# Viehmann_GPS_2015.net
KiCad netlist of a schematic drawn in EAGLE
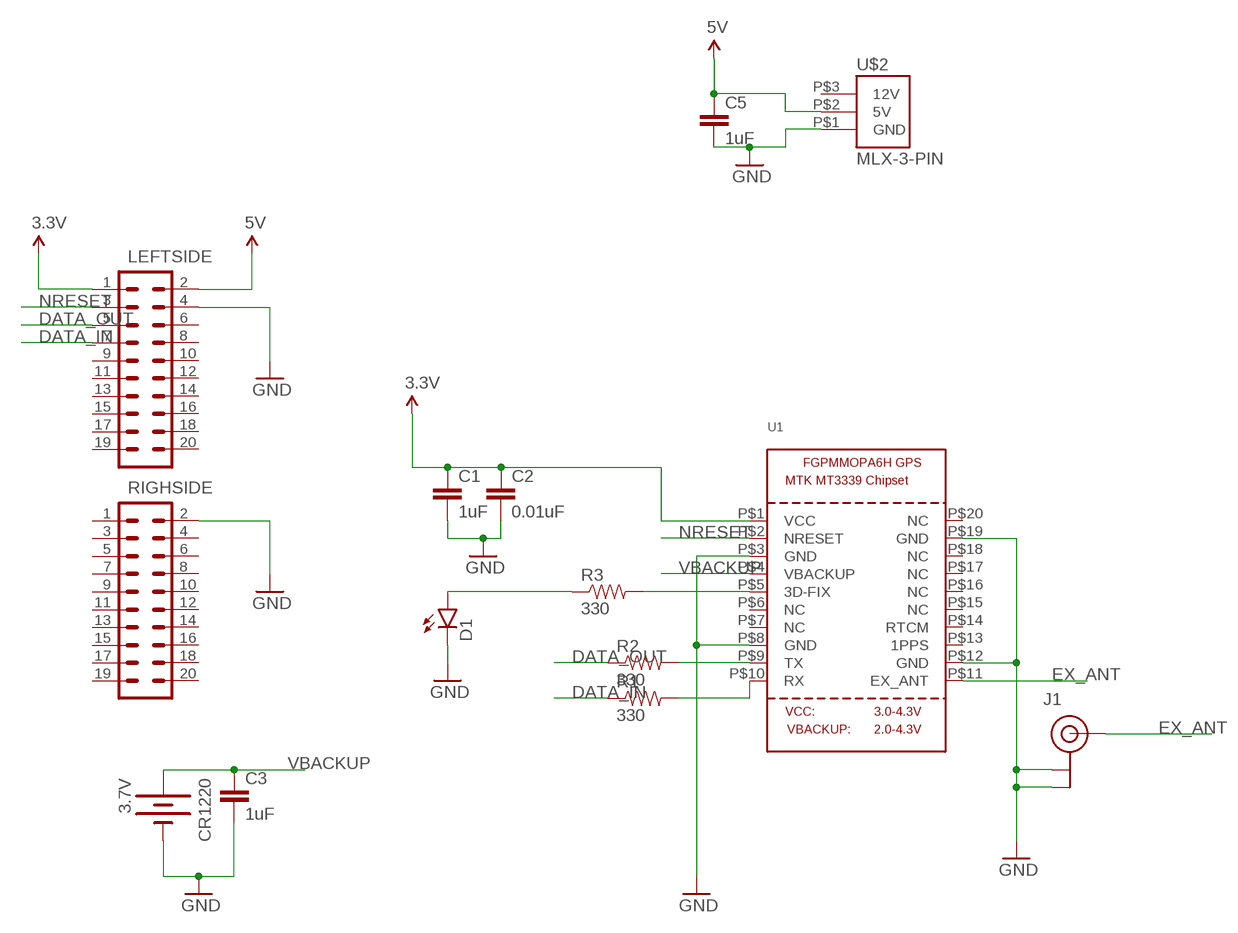
[diagram p0: schematic, sheet 1]

(export (version "E")
  (design (tool "Eeschema 10.0.6"))
  (components
    (comp (ref "C1")
      (value "1uF")
      (footprint "eagle-import:1206")
      (libsource (lib "eagle-import") (part "CAP1206"))
    )
    (comp (ref "C2")
      (value "0.01uF")
      (footprint "eagle-import:1206")
      (libsource (lib "eagle-import") (part "CAP1206"))
    )
    (comp (ref "C3")
      (value "1uF")
      (footprint "eagle-import:1206")
      (libsource (lib "eagle-import") (part "CAP1206"))
    )
    (comp (ref "C5")
      (value "1uF")
      (footprint "eagle-import:1206")
      (libsource (lib "eagle-import") (part "CAP1206"))
    )
    (comp (ref "CR1220")
      (value "3.7V")
      (footprint "eagle-import:BATTCON_12MM")
      (libsource (lib "eagle-import") (part "BATTERY12MM"))
    )
    (comp (ref "D1")
      (value "LED1206")
      (footprint "eagle-import:LED-1206")
      (libsource (lib "eagle-import") (part "LED1206"))
    )
    (comp (ref "J1")
      (value "U.FL")
      (footprint "eagle-import:U.FL")
      (libsource (lib "eagle-import") (part "U.FL"))
    )
    (comp (ref "LEFTSIDE")
      (value "M10X2")
      (footprint "eagle-import:2X10")
      (libsource (lib "eagle-import") (part "M10X2"))
    )
    (comp (ref "R1")
      (value "330")
      (footprint "eagle-import:1206")
      (libsource (lib "eagle-import") (part "RESISTOR1206"))
    )
    (comp (ref "R2")
      (value "330")
      (footprint "eagle-import:1206")
      (libsource (lib "eagle-import") (part "RESISTOR1206"))
    )
    (comp (ref "R3")
      (value "330")
      (footprint "eagle-import:1206")
      (libsource (lib "eagle-import") (part "RESISTOR1206"))
    )
    (comp (ref "RIGHSIDE")
      (value "M10X2")
      (footprint "eagle-import:2X10")
      (libsource (lib "eagle-import") (part "M10X2"))
    )
    (comp (ref "U$2")
      (value "MLX-3-PIN")
      (footprint "eagle-import:MLX-3-PIN-SOCKET")
      (libsource (lib "eagle-import") (part "MLX-3-PIN"))
    )
    (comp (ref "U1")
      (value "GPS_FGPMMOPA6H")
      (footprint "eagle-import:FGPMMOPA6H")
      (libsource (lib "eagle-import") (part "GPS_FGPMMOPA6H"))
    )
  )
  (nets
    (net (code "1") (name "/DATA_IN") (class "Default")
      (node (ref "LEFTSIDE") (pin "7") (pinfunction "7_7") (pintype "passive"))
      (node (ref "R1") (pin "1") (pinfunction "1_1") (pintype "passive"))
    )
    (net (code "2") (name "/DATA_OUT") (class "Default")
      (node (ref "LEFTSIDE") (pin "5") (pinfunction "5_5") (pintype "passive"))
      (node (ref "R2") (pin "1") (pinfunction "1_1") (pintype "passive"))
    )
    (net (code "3") (name "/EX_ANT") (class "Default")
      (node (ref "J1") (pin "P$3") (pinfunction "SIGNAL_P$3") (pintype "bidirectional"))
      (node (ref "U1") (pin "P$11") (pinfunction "EX_ANT_P$11") (pintype "bidirectional"))
    )
    (net (code "4") (name "/NRESET") (class "Default")
      (node (ref "LEFTSIDE") (pin "3") (pinfunction "3_3") (pintype "passive"))
      (node (ref "U1") (pin "P$2") (pinfunction "NRESET_P$2") (pintype "bidirectional"))
    )
    (net (code "5") (name "/VBACKUP") (class "Default")
      (node (ref "C3") (pin "1") (pinfunction "1_1") (pintype "passive"))
      (node (ref "CR1220") (pin "PWR@1") (pinfunction "+_PWR@1") (pintype "power_in"))
      (node (ref "U1") (pin "P$4") (pinfunction "VBACKUP_P$4") (pintype "bidirectional"))
    )
    (net (code "6") (name "3.3V") (class "Default")
      (node (ref "C1") (pin "1") (pinfunction "1_1") (pintype "passive"))
      (node (ref "C2") (pin "1") (pinfunction "1_1") (pintype "passive"))
      (node (ref "LEFTSIDE") (pin "1") (pinfunction "1_1") (pintype "passive"))
      (node (ref "U1") (pin "P$1") (pinfunction "VCC_P$1") (pintype "bidirectional"))
    )
    (net (code "7") (name "5V") (class "Default")
      (node (ref "C5") (pin "1") (pinfunction "1_1") (pintype "passive"))
      (node (ref "LEFTSIDE") (pin "2") (pinfunction "2_2") (pintype "passive"))
      (node (ref "U$2") (pin "P$2") (pinfunction "5V_P$2") (pintype "bidirectional"))
    )
    (net (code "8") (name "GND") (class "Default")
      (node (ref "C1") (pin "2") (pinfunction "2_2") (pintype "passive"))
      (node (ref "C2") (pin "2") (pinfunction "2_2") (pintype "passive"))
      (node (ref "C3") (pin "2") (pinfunction "2_2") (pintype "passive"))
      (node (ref "C5") (pin "2") (pinfunction "2_2") (pintype "passive"))
      (node (ref "CR1220") (pin "GND") (pinfunction "-_GND") (pintype "power_in"))
      (node (ref "D1") (pin "C") (pinfunction "C_C") (pintype "passive"))
      (node (ref "J1") (pin "P$1") (pinfunction "GND_P$1") (pintype "bidirectional"))
      (node (ref "J1") (pin "P$2") (pinfunction "GND_P$2") (pintype "bidirectional"))
      (node (ref "LEFTSIDE") (pin "4") (pinfunction "4_4") (pintype "passive"))
      (node (ref "RIGHSIDE") (pin "2") (pinfunction "2_2") (pintype "passive"))
      (node (ref "U$2") (pin "P$1") (pinfunction "GND_P$1") (pintype "bidirectional"))
      (node (ref "U1") (pin "P$12") (pinfunction "GND_P$12") (pintype "bidirectional"))
      (node (ref "U1") (pin "P$19") (pinfunction "GND_P$19") (pintype "bidirectional"))
      (node (ref "U1") (pin "P$3") (pinfunction "GND_P$3") (pintype "bidirectional"))
      (node (ref "U1") (pin "P$8") (pinfunction "GND_P$8") (pintype "bidirectional"))
    )
    (net (code "9") (name "Net-(D1-PadA)") (class "Default")
      (node (ref "D1") (pin "A") (pinfunction "A_A") (pintype "passive"))
      (node (ref "R3") (pin "1") (pinfunction "1_1") (pintype "passive"))
    )
    (net (code "10") (name "Net-(U1-3D-FIX)") (class "Default")
      (node (ref "R3") (pin "2") (pinfunction "2_2") (pintype "passive"))
      (node (ref "U1") (pin "P$5") (pinfunction "3D-FIX_P$5") (pintype "bidirectional"))
    )
    (net (code "11") (name "Net-(U1-RX)") (class "Default")
      (node (ref "R1") (pin "2") (pinfunction "2_2") (pintype "passive"))
      (node (ref "U1") (pin "P$10") (pinfunction "RX_P$10") (pintype "bidirectional"))
    )
    (net (code "12") (name "Net-(U1-TX)") (class "Default")
      (node (ref "R2") (pin "2") (pinfunction "2_2") (pintype "passive"))
      (node (ref "U1") (pin "P$9") (pinfunction "TX_P$9") (pintype "bidirectional"))
    )
    (net (code "13") (name "unconnected-(LEFTSIDE-Pad6)") (class "Default")
      (node (ref "LEFTSIDE") (pin "6") (pinfunction "6_6") (pintype "passive"))
    )
    (net (code "14") (name "unconnected-(LEFTSIDE-Pad8)") (class "Default")
      (node (ref "LEFTSIDE") (pin "8") (pinfunction "8_8") (pintype "passive"))
    )
    (net (code "15") (name "unconnected-(LEFTSIDE-Pad9)") (class "Default")
      (node (ref "LEFTSIDE") (pin "9") (pinfunction "9_9") (pintype "passive"))
    )
    (net (code "16") (name "unconnected-(LEFTSIDE-Pad10)") (class "Default")
      (node (ref "LEFTSIDE") (pin "10") (pinfunction "10_10") (pintype "passive"))
    )
    (net (code "17") (name "unconnected-(LEFTSIDE-Pad11)") (class "Default")
      (node (ref "LEFTSIDE") (pin "11") (pinfunction "11_11") (pintype "passive"))
    )
    (net (code "18") (name "unconnected-(LEFTSIDE-Pad12)") (class "Default")
      (node (ref "LEFTSIDE") (pin "12") (pinfunction "12_12") (pintype "passive"))
    )
    (net (code "19") (name "unconnected-(LEFTSIDE-Pad13)") (class "Default")
      (node (ref "LEFTSIDE") (pin "13") (pinfunction "13_13") (pintype "passive"))
    )
    (net (code "20") (name "unconnected-(LEFTSIDE-Pad14)") (class "Default")
      (node (ref "LEFTSIDE") (pin "14") (pinfunction "14_14") (pintype "passive"))
    )
    (net (code "21") (name "unconnected-(LEFTSIDE-Pad15)") (class "Default")
      (node (ref "LEFTSIDE") (pin "15") (pinfunction "15_15") (pintype "passive"))
    )
    (net (code "22") (name "unconnected-(LEFTSIDE-Pad16)") (class "Default")
      (node (ref "LEFTSIDE") (pin "16") (pinfunction "16_16") (pintype "passive"))
    )
    (net (code "23") (name "unconnected-(LEFTSIDE-Pad17)") (class "Default")
      (node (ref "LEFTSIDE") (pin "17") (pinfunction "17_17") (pintype "passive"))
    )
    (net (code "24") (name "unconnected-(LEFTSIDE-Pad18)") (class "Default")
      (node (ref "LEFTSIDE") (pin "18") (pinfunction "18_18") (pintype "passive"))
    )
    (net (code "25") (name "unconnected-(LEFTSIDE-Pad19)") (class "Default")
      (node (ref "LEFTSIDE") (pin "19") (pinfunction "19_19") (pintype "passive"))
    )
    (net (code "26") (name "unconnected-(LEFTSIDE-Pad20)") (class "Default")
      (node (ref "LEFTSIDE") (pin "20") (pinfunction "20_20") (pintype "passive"))
    )
    (net (code "27") (name "unconnected-(RIGHSIDE-Pad1)") (class "Default")
      (node (ref "RIGHSIDE") (pin "1") (pinfunction "1_1") (pintype "passive"))
    )
    (net (code "28") (name "unconnected-(RIGHSIDE-Pad3)") (class "Default")
      (node (ref "RIGHSIDE") (pin "3") (pinfunction "3_3") (pintype "passive"))
    )
    (net (code "29") (name "unconnected-(RIGHSIDE-Pad4)") (class "Default")
      (node (ref "RIGHSIDE") (pin "4") (pinfunction "4_4") (pintype "passive"))
    )
    (net (code "30") (name "unconnected-(RIGHSIDE-Pad5)") (class "Default")
      (node (ref "RIGHSIDE") (pin "5") (pinfunction "5_5") (pintype "passive"))
    )
    (net (code "31") (name "unconnected-(RIGHSIDE-Pad6)") (class "Default")
      (node (ref "RIGHSIDE") (pin "6") (pinfunction "6_6") (pintype "passive"))
    )
    (net (code "32") (name "unconnected-(RIGHSIDE-Pad7)") (class "Default")
      (node (ref "RIGHSIDE") (pin "7") (pinfunction "7_7") (pintype "passive"))
    )
    (net (code "33") (name "unconnected-(RIGHSIDE-Pad8)") (class "Default")
      (node (ref "RIGHSIDE") (pin "8") (pinfunction "8_8") (pintype "passive"))
    )
    (net (code "34") (name "unconnected-(RIGHSIDE-Pad9)") (class "Default")
      (node (ref "RIGHSIDE") (pin "9") (pinfunction "9_9") (pintype "passive"))
    )
    (net (code "35") (name "unconnected-(RIGHSIDE-Pad10)") (class "Default")
      (node (ref "RIGHSIDE") (pin "10") (pinfunction "10_10") (pintype "passive"))
    )
    (net (code "36") (name "unconnected-(RIGHSIDE-Pad11)") (class "Default")
      (node (ref "RIGHSIDE") (pin "11") (pinfunction "11_11") (pintype "passive"))
    )
    (net (code "37") (name "unconnected-(RIGHSIDE-Pad12)") (class "Default")
      (node (ref "RIGHSIDE") (pin "12") (pinfunction "12_12") (pintype "passive"))
    )
    (net (code "38") (name "unconnected-(RIGHSIDE-Pad13)") (class "Default")
      (node (ref "RIGHSIDE") (pin "13") (pinfunction "13_13") (pintype "passive"))
    )
    (net (code "39") (name "unconnected-(RIGHSIDE-Pad14)") (class "Default")
      (node (ref "RIGHSIDE") (pin "14") (pinfunction "14_14") (pintype "passive"))
    )
    (net (code "40") (name "unconnected-(RIGHSIDE-Pad15)") (class "Default")
      (node (ref "RIGHSIDE") (pin "15") (pinfunction "15_15") (pintype "passive"))
    )
    (net (code "41") (name "unconnected-(RIGHSIDE-Pad16)") (class "Default")
      (node (ref "RIGHSIDE") (pin "16") (pinfunction "16_16") (pintype "passive"))
    )
    (net (code "42") (name "unconnected-(RIGHSIDE-Pad17)") (class "Default")
      (node (ref "RIGHSIDE") (pin "17") (pinfunction "17_17") (pintype "passive"))
    )
    (net (code "43") (name "unconnected-(RIGHSIDE-Pad18)") (class "Default")
      (node (ref "RIGHSIDE") (pin "18") (pinfunction "18_18") (pintype "passive"))
    )
    (net (code "44") (name "unconnected-(RIGHSIDE-Pad19)") (class "Default")
      (node (ref "RIGHSIDE") (pin "19") (pinfunction "19_19") (pintype "passive"))
    )
    (net (code "45") (name "unconnected-(RIGHSIDE-Pad20)") (class "Default")
      (node (ref "RIGHSIDE") (pin "20") (pinfunction "20_20") (pintype "passive"))
    )
    (net (code "46") (name "unconnected-(U$2-12V-PadP$3)") (class "Default")
      (node (ref "U$2") (pin "P$3") (pinfunction "12V_P$3") (pintype "bidirectional"))
    )
    (net (code "47") (name "unconnected-(U1-1PPS-PadP$13)") (class "Default")
      (node (ref "U1") (pin "P$13") (pinfunction "1PPS_P$13") (pintype "bidirectional"))
    )
    (net (code "48") (name "unconnected-(U1-NC-PadP$6)") (class "Default")
      (node (ref "U1") (pin "P$6") (pinfunction "NC_P$6") (pintype "bidirectional"))
    )
    (net (code "49") (name "unconnected-(U1-NC-PadP$7)") (class "Default")
      (node (ref "U1") (pin "P$7") (pinfunction "NC_P$7") (pintype "bidirectional"))
    )
    (net (code "50") (name "unconnected-(U1-NC-PadP$15)") (class "Default")
      (node (ref "U1") (pin "P$15") (pinfunction "NC_P$15") (pintype "bidirectional"))
    )
    (net (code "51") (name "unconnected-(U1-NC-PadP$16)") (class "Default")
      (node (ref "U1") (pin "P$16") (pinfunction "NC_P$16") (pintype "bidirectional"))
    )
    (net (code "52") (name "unconnected-(U1-NC-PadP$17)") (class "Default")
      (node (ref "U1") (pin "P$17") (pinfunction "NC_P$17") (pintype "bidirectional"))
    )
    (net (code "53") (name "unconnected-(U1-NC-PadP$18)") (class "Default")
      (node (ref "U1") (pin "P$18") (pinfunction "NC_P$18") (pintype "bidirectional"))
    )
    (net (code "54") (name "unconnected-(U1-NC-PadP$20)") (class "Default")
      (node (ref "U1") (pin "P$20") (pinfunction "NC_P$20") (pintype "bidirectional"))
    )
    (net (code "55") (name "unconnected-(U1-RTCM-PadP$14)") (class "Default")
      (node (ref "U1") (pin "P$14") (pinfunction "RTCM_P$14") (pintype "bidirectional"))
    )
  )
)
